# SparkFun_On_Screen_Display-MAX7456.net
KiCad netlist of a schematic drawn in EAGLE
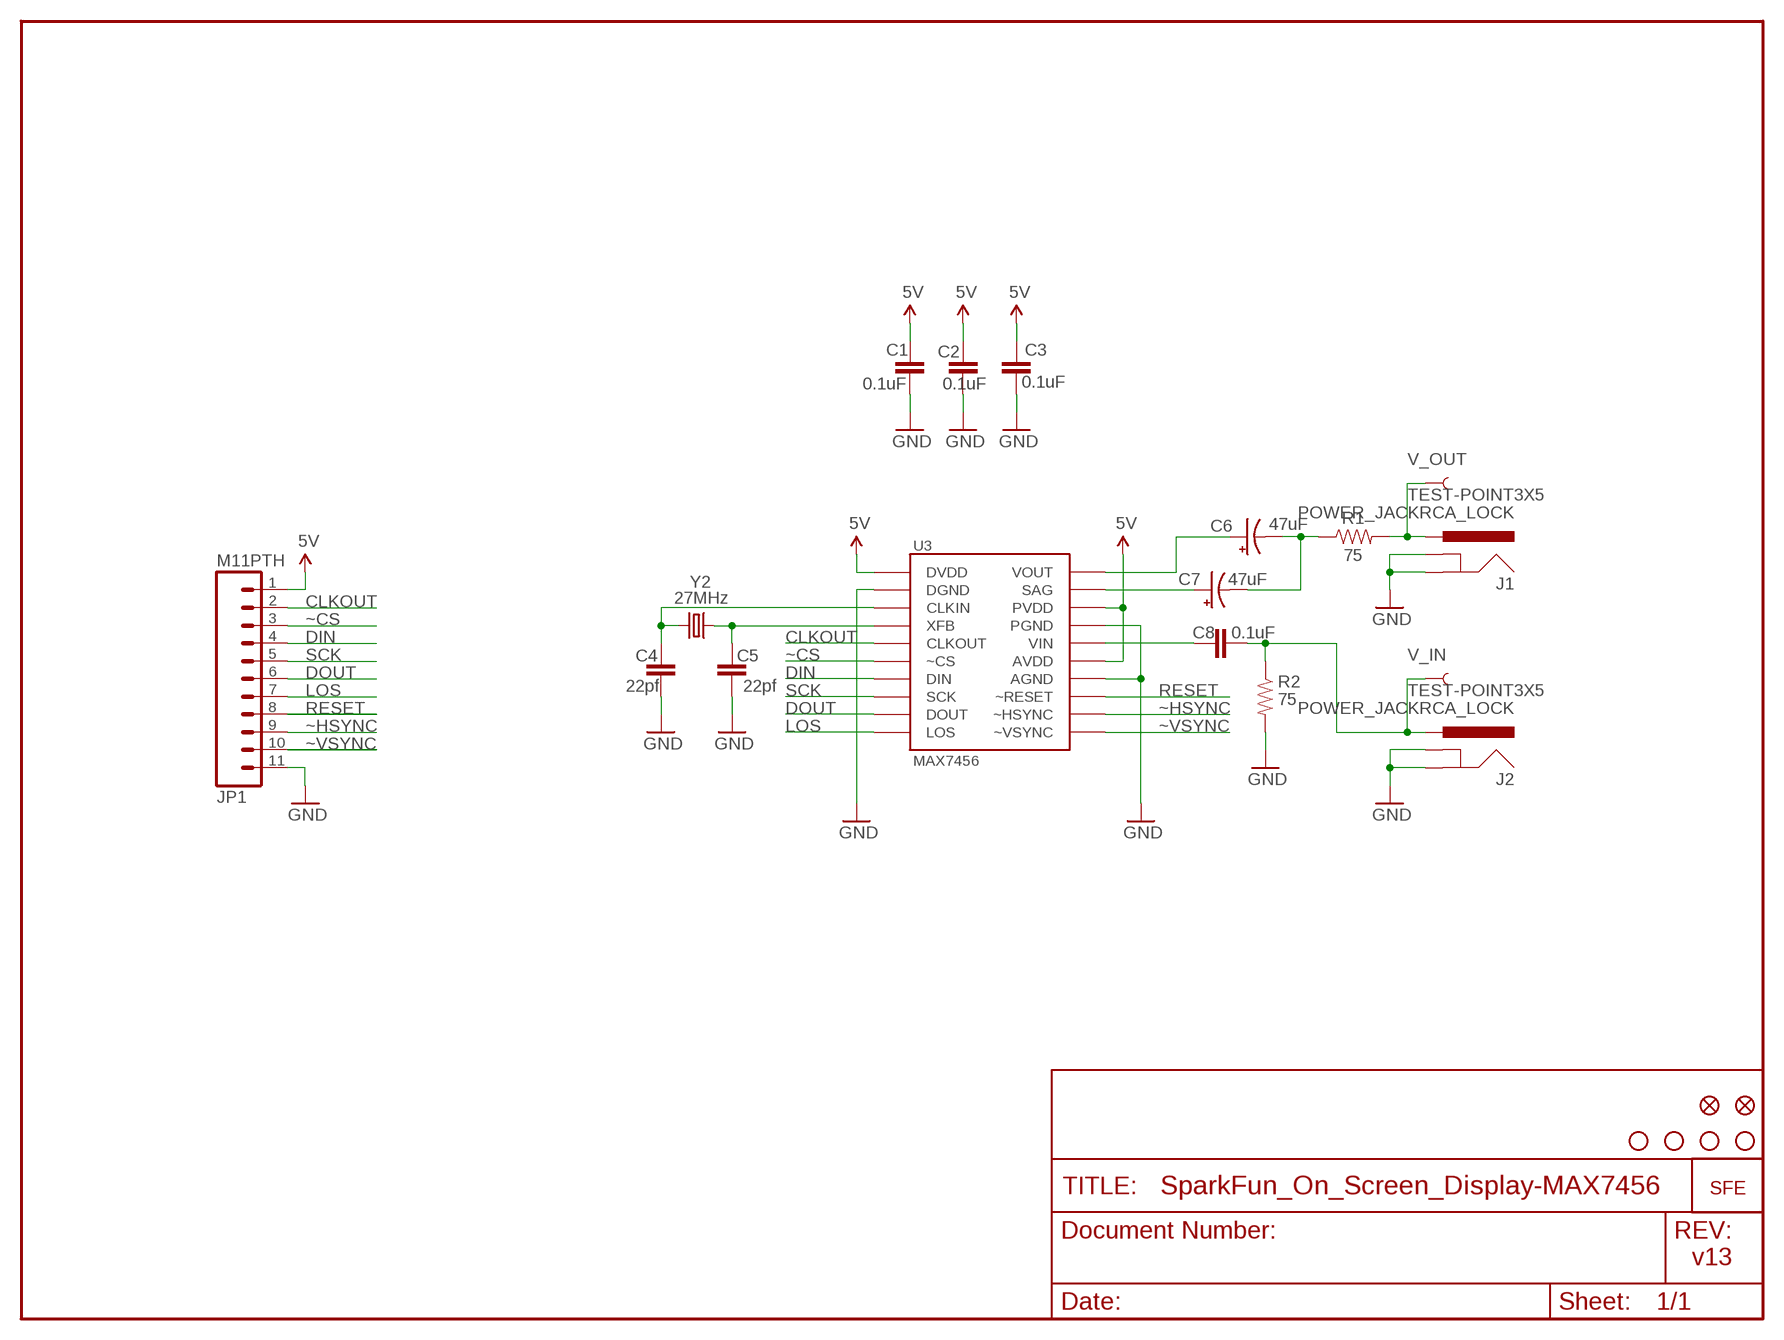
[diagram p0: schematic, sheet 1]

(export (version "E")
  (design (tool "Eeschema 10.0.6"))
  (components
    (comp (ref "C1")
      (value "0.1uF")
      (footprint "eagle-import:C0402")
      (libsource (lib "eagle-import") (part "CAP0402"))
    )
    (comp (ref "C2")
      (value "0.1uF")
      (footprint "eagle-import:C0402")
      (libsource (lib "eagle-import") (part "CAP0402"))
    )
    (comp (ref "C3")
      (value "0.1uF")
      (footprint "eagle-import:C0402")
      (libsource (lib "eagle-import") (part "CAP0402"))
    )
    (comp (ref "C4")
      (value "22pf")
      (footprint "eagle-import:C0402")
      (libsource (lib "eagle-import") (part "CAP0402"))
    )
    (comp (ref "C5")
      (value "22pf")
      (footprint "eagle-import:C0402")
      (libsource (lib "eagle-import") (part "CAP0402"))
    )
    (comp (ref "C6")
      (value "47uF")
      (footprint "eagle-import:EIA3528")
      (libsource (lib "eagle-import") (part "CAP_POL3528"))
    )
    (comp (ref "C7")
      (value "47uF")
      (footprint "eagle-import:EIA3528")
      (libsource (lib "eagle-import") (part "CAP_POL3528"))
    )
    (comp (ref "C8")
      (value "0.1uF")
      (footprint "eagle-import:C0402")
      (libsource (lib "eagle-import") (part "CAP0402"))
    )
    (comp (ref "J1")
      (value "POWER_JACKRCA_LOCK")
      (footprint "eagle-import:RCA_LOCK")
      (libsource (lib "eagle-import") (part "POWER_JACKRCA_LOCK"))
    )
    (comp (ref "J2")
      (value "POWER_JACKRCA_LOCK")
      (footprint "eagle-import:RCA_LOCK")
      (libsource (lib "eagle-import") (part "POWER_JACKRCA_LOCK"))
    )
    (comp (ref "JP1")
      (value "M11PTH")
      (footprint "eagle-import:1X11")
      (libsource (lib "eagle-import") (part "M11PTH"))
    )
    (comp (ref "R1")
      (value "75")
      (footprint "eagle-import:C0402")
      (libsource (lib "eagle-import") (part "RESISTOR0402"))
    )
    (comp (ref "R2")
      (value "75")
      (footprint "eagle-import:C0402")
      (libsource (lib "eagle-import") (part "RESISTOR0402"))
    )
    (comp (ref "U$2")
      (value "STAND-OFF")
      (footprint "eagle-import:STAND-OFF")
      (libsource (lib "eagle-import") (part "STAND-OFF"))
    )
    (comp (ref "U$8")
      (value "LOGO-SFENEW")
      (footprint "eagle-import:SFE-NEW-WEBLOGO")
      (libsource (lib "eagle-import") (part "LOGO-SFENEW"))
    )
    (comp (ref "U$9")
      (value "FIDUCIAL1X2")
      (footprint "eagle-import:FIDUCIAL-1X2")
      (libsource (lib "eagle-import") (part "FIDUCIAL1X2"))
    )
    (comp (ref "U$10")
      (value "FIDUCIAL1X2")
      (footprint "eagle-import:FIDUCIAL-1X2")
      (libsource (lib "eagle-import") (part "FIDUCIAL1X2"))
    )
    (comp (ref "U$12")
      (value "STAND-OFF")
      (footprint "eagle-import:STAND-OFF")
      (libsource (lib "eagle-import") (part "STAND-OFF"))
    )
    (comp (ref "U$13")
      (value "STAND-OFF")
      (footprint "eagle-import:STAND-OFF")
      (libsource (lib "eagle-import") (part "STAND-OFF"))
    )
    (comp (ref "U$14")
      (value "STAND-OFF")
      (footprint "eagle-import:STAND-OFF")
      (libsource (lib "eagle-import") (part "STAND-OFF"))
    )
    (comp (ref "U3")
      (value "MAX7456")
      (footprint "eagle-import:TSSOP28")
      (libsource (lib "eagle-import") (part "MAX7456"))
    )
    (comp (ref "V_IN")
      (value "TEST-POINT3X5")
      (footprint "eagle-import:PAD.03X.05")
      (libsource (lib "eagle-import") (part "TEST-POINT3X5"))
    )
    (comp (ref "V_OUT")
      (value "TEST-POINT3X5")
      (footprint "eagle-import:PAD.03X.05")
      (libsource (lib "eagle-import") (part "TEST-POINT3X5"))
    )
    (comp (ref "Y2")
      (value "27MHz")
      (footprint "eagle-import:CRYSTAL-SMD-5X3")
      (libsource (lib "eagle-import") (part "CRYSTAL5X3"))
    )
  )
  (nets
    (net (code "1") (name "/CLKOUT") (class "Default")
      (node (ref "JP1") (pin "2") (pinfunction "2_2") (pintype "passive"))
      (node (ref "U3") (pin "7") (pinfunction "CLKOUT_7") (pintype "bidirectional"))
    )
    (net (code "2") (name "/DIN") (class "Default")
      (node (ref "JP1") (pin "4") (pinfunction "4_4") (pintype "passive"))
      (node (ref "U3") (pin "9") (pinfunction "DIN_9") (pintype "bidirectional"))
    )
    (net (code "3") (name "/DOUT") (class "Default")
      (node (ref "JP1") (pin "6") (pinfunction "6_6") (pintype "passive"))
      (node (ref "U3") (pin "11") (pinfunction "DOUT_11") (pintype "bidirectional"))
    )
    (net (code "4") (name "/LOS") (class "Default")
      (node (ref "JP1") (pin "7") (pinfunction "7_7") (pintype "passive"))
      (node (ref "U3") (pin "12") (pinfunction "LOS_12") (pintype "bidirectional"))
    )
    (net (code "5") (name "/RESET") (class "Default")
      (node (ref "JP1") (pin "8") (pinfunction "8_8") (pintype "passive"))
      (node (ref "U3") (pin "19") (pinfunction "~{RESET}_19") (pintype "bidirectional"))
    )
    (net (code "6") (name "/SCK") (class "Default")
      (node (ref "JP1") (pin "5") (pinfunction "5_5") (pintype "passive"))
      (node (ref "U3") (pin "10") (pinfunction "SCK_10") (pintype "bidirectional"))
    )
    (net (code "7") (name "/~{CS}") (class "Default")
      (node (ref "JP1") (pin "3") (pinfunction "3_3") (pintype "passive"))
      (node (ref "U3") (pin "8") (pinfunction "~{CS}_8") (pintype "bidirectional"))
    )
    (net (code "8") (name "/~{HSYNC}") (class "Default")
      (node (ref "JP1") (pin "9") (pinfunction "9_9") (pintype "passive"))
      (node (ref "U3") (pin "18") (pinfunction "~{HSYNC}_18") (pintype "bidirectional"))
    )
    (net (code "9") (name "/~{VSYNC}") (class "Default")
      (node (ref "JP1") (pin "10") (pinfunction "10_10") (pintype "passive"))
      (node (ref "U3") (pin "17") (pinfunction "~{VSYNC}_17") (pintype "bidirectional"))
    )
    (net (code "10") (name "5V") (class "Default")
      (node (ref "C1") (pin "2") (pinfunction "2_2") (pintype "passive"))
      (node (ref "C2") (pin "2") (pinfunction "2_2") (pintype "passive"))
      (node (ref "C3") (pin "2") (pinfunction "2_2") (pintype "passive"))
      (node (ref "JP1") (pin "1") (pinfunction "1_1") (pintype "passive"))
      (node (ref "U3") (pin "21") (pinfunction "AVDD_21") (pintype "bidirectional"))
      (node (ref "U3") (pin "24") (pinfunction "PVDD_24") (pintype "bidirectional"))
      (node (ref "U3") (pin "3") (pinfunction "DVDD_3") (pintype "bidirectional"))
    )
    (net (code "11") (name "GND") (class "Default")
      (node (ref "C1") (pin "1") (pinfunction "1_1") (pintype "passive"))
      (node (ref "C2") (pin "1") (pinfunction "1_1") (pintype "passive"))
      (node (ref "C3") (pin "1") (pinfunction "1_1") (pintype "passive"))
      (node (ref "C4") (pin "1") (pinfunction "1_1") (pintype "passive"))
      (node (ref "C5") (pin "1") (pinfunction "1_1") (pintype "passive"))
      (node (ref "J1") (pin "BARREL") (pinfunction "GND_BARREL") (pintype "bidirectional"))
      (node (ref "J1") (pin "SPRING") (pinfunction "GNDBREAK_SPRING") (pintype "bidirectional"))
      (node (ref "J2") (pin "BARREL") (pinfunction "GND_BARREL") (pintype "bidirectional"))
      (node (ref "J2") (pin "SPRING") (pinfunction "GNDBREAK_SPRING") (pintype "bidirectional"))
      (node (ref "JP1") (pin "11") (pinfunction "11_11") (pintype "passive"))
      (node (ref "R2") (pin "2") (pinfunction "2_2") (pintype "passive"))
      (node (ref "U3") (pin "20") (pinfunction "AGND_20") (pintype "bidirectional"))
      (node (ref "U3") (pin "23") (pinfunction "PGND_23") (pintype "bidirectional"))
      (node (ref "U3") (pin "4") (pinfunction "DGND_4") (pintype "bidirectional"))
    )
    (net (code "12") (name "Net-(C6-+)") (class "Default")
      (node (ref "C6") (pin "A") (pinfunction "+_A") (pintype "passive"))
      (node (ref "U3") (pin "26") (pinfunction "VOUT_26") (pintype "bidirectional"))
    )
    (net (code "13") (name "Net-(C6--)") (class "Default")
      (node (ref "C6") (pin "C") (pinfunction "-_C") (pintype "passive"))
      (node (ref "C7") (pin "C") (pinfunction "-_C") (pintype "passive"))
      (node (ref "R1") (pin "1") (pinfunction "1_1") (pintype "passive"))
    )
    (net (code "14") (name "Net-(C7-+)") (class "Default")
      (node (ref "C7") (pin "A") (pinfunction "+_A") (pintype "passive"))
      (node (ref "U3") (pin "25") (pinfunction "SAG_25") (pintype "bidirectional"))
    )
    (net (code "15") (name "Net-(J1-PWR)") (class "Default")
      (node (ref "J1") (pin "BREAK") (pinfunction "PWR_BREAK") (pintype "bidirectional"))
      (node (ref "R1") (pin "2") (pinfunction "2_2") (pintype "passive"))
      (node (ref "V_OUT") (pin "P$1") (pinfunction "1_P$1") (pintype "bidirectional"))
    )
    (net (code "16") (name "Net-(J2-PWR)") (class "Default")
      (node (ref "C8") (pin "1") (pinfunction "1_1") (pintype "passive"))
      (node (ref "J2") (pin "BREAK") (pinfunction "PWR_BREAK") (pintype "bidirectional"))
      (node (ref "R2") (pin "1") (pinfunction "1_1") (pintype "passive"))
      (node (ref "V_IN") (pin "P$1") (pinfunction "1_P$1") (pintype "bidirectional"))
    )
    (net (code "17") (name "Net-(U3-CLKIN)") (class "Default")
      (node (ref "C4") (pin "2") (pinfunction "2_2") (pintype "passive"))
      (node (ref "U3") (pin "5") (pinfunction "CLKIN_5") (pintype "bidirectional"))
      (node (ref "Y2") (pin "3") (pinfunction "2_3") (pintype "passive"))
    )
    (net (code "18") (name "Net-(U3-VIN)") (class "Default")
      (node (ref "C8") (pin "2") (pinfunction "2_2") (pintype "passive"))
      (node (ref "U3") (pin "22") (pinfunction "VIN_22") (pintype "bidirectional"))
    )
    (net (code "19") (name "Net-(U3-XFB)") (class "Default")
      (node (ref "C5") (pin "2") (pinfunction "2_2") (pintype "passive"))
      (node (ref "U3") (pin "6") (pinfunction "XFB_6") (pintype "bidirectional"))
      (node (ref "Y2") (pin "1") (pinfunction "1_1") (pintype "passive"))
    )
  )
)
